# GyroAccel.net
KiCad netlist of a schematic drawn in Altium Designer
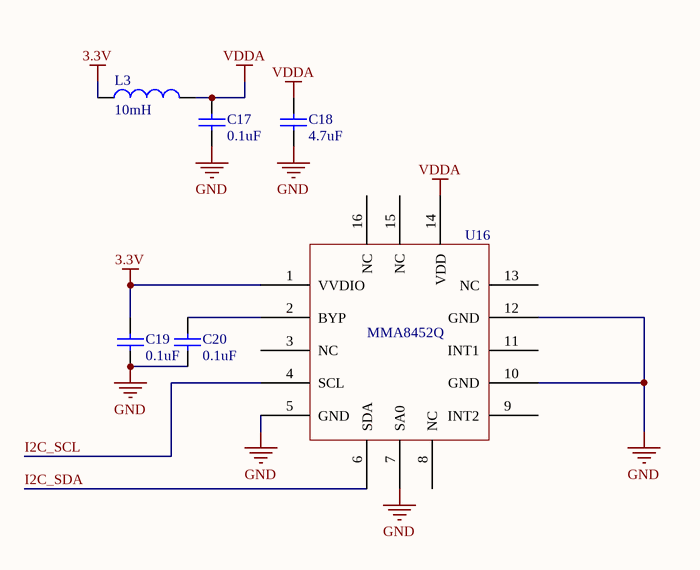
[diagram p0: GyroAccel.SchDoc]

(export (version "E")
  (design (tool "Eeschema 10.0.6"))
  (components
    (comp (ref "C17")
      (value "0.1uF")
      (footprint "CAPC1005L")
      (description "Capacitor (Semiconductor SIM Model)")
      (fields (field (name "Comment") "Cap Semi") (field (name "PUBLISHER") "Altium Limited"))
      (libsource (lib "Miscellaneous Devices") (part "Cap Semi"))
    )
    (comp (ref "C18")
      (value "4.7uF")
      (footprint "CAPC1608L")
      (description "Capacitor (Semiconductor SIM Model)")
      (fields (field (name "Comment") "Cap Semi") (field (name "PUBLISHER") "Altium Limited"))
      (libsource (lib "Miscellaneous Devices") (part "Cap Semi"))
    )
    (comp (ref "C19")
      (value "0.1uF")
      (footprint "CAPC1005L")
      (description "Capacitor (Semiconductor SIM Model)")
      (fields (field (name "Comment") "Cap Semi") (field (name "PUBLISHER") "Altium Limited"))
      (libsource (lib "Miscellaneous Devices") (part "Cap Semi"))
    )
    (comp (ref "C20")
      (value "0.1uF")
      (footprint "CAPC1005L")
      (description "Capacitor (Semiconductor SIM Model)")
      (fields (field (name "Comment") "Cap Semi") (field (name "PUBLISHER") "Altium Limited"))
      (libsource (lib "Miscellaneous Devices") (part "Cap Semi"))
    )
    (comp (ref "L3")
      (value "10mH")
      (footprint "INDC2012L")
      (description "Inductor")
      (fields (field (name "PUBLISHER") "Altium Limited"))
      (libsource (lib "Miscellaneous Devices") (part "Inductor"))
    )
    (comp (ref "U16") (value "MMA8452Q") (footprint "MMA8452Q") (libsource (lib "mrone") (part "MMA8452Q")))
  )
  (nets
    (net (code "1") (name "/I2C_SCL") (class "Default")
      (node (ref "U16") (pin "4") (pinfunction "SCL_4") (pintype "passive"))
    )
    (net (code "2") (name "/I2C_SDA") (class "Default")
      (node (ref "U16") (pin "6") (pinfunction "SDA_6") (pintype "passive"))
    )
    (net (code "3") (name "3.3V") (class "Default")
      (node (ref "C19") (pin "2") (pinfunction "2_2") (pintype "passive"))
      (node (ref "L3") (pin "2") (pinfunction "2_2") (pintype "passive"))
      (node (ref "U16") (pin "1") (pinfunction "VVDIO_1") (pintype "passive"))
    )
    (net (code "4") (name "GND") (class "Default")
      (node (ref "C17") (pin "1") (pinfunction "1_1") (pintype "passive"))
      (node (ref "C18") (pin "1") (pinfunction "1_1") (pintype "passive"))
      (node (ref "C19") (pin "1") (pinfunction "1_1") (pintype "passive"))
      (node (ref "C20") (pin "1") (pinfunction "1_1") (pintype "passive"))
      (node (ref "U16") (pin "10") (pinfunction "GND_10") (pintype "passive"))
      (node (ref "U16") (pin "12") (pinfunction "GND_12") (pintype "passive"))
      (node (ref "U16") (pin "5") (pinfunction "GND_5") (pintype "passive"))
      (node (ref "U16") (pin "7") (pinfunction "SA0_7") (pintype "passive"))
    )
    (net (code "5") (name "Net-(U16-BYP)") (class "Default")
      (node (ref "C20") (pin "2") (pinfunction "2_2") (pintype "passive"))
      (node (ref "U16") (pin "2") (pinfunction "BYP_2") (pintype "passive"))
    )
    (net (code "6") (name "VDDA") (class "Default")
      (node (ref "C17") (pin "2") (pinfunction "2_2") (pintype "passive"))
      (node (ref "C18") (pin "2") (pinfunction "2_2") (pintype "passive"))
      (node (ref "L3") (pin "1") (pinfunction "1_1") (pintype "passive"))
      (node (ref "U16") (pin "14") (pinfunction "VDD_14") (pintype "passive"))
    )
    (net (code "7") (name "unconnected-(U16-INT1-Pad11)") (class "Default")
      (node (ref "U16") (pin "11") (pinfunction "INT1_11") (pintype "passive"))
    )
    (net (code "8") (name "unconnected-(U16-INT2-Pad9)") (class "Default")
      (node (ref "U16") (pin "9") (pinfunction "INT2_9") (pintype "passive"))
    )
    (net (code "9") (name "unconnected-(U16-NC-Pad3)") (class "Default")
      (node (ref "U16") (pin "3") (pinfunction "NC_3") (pintype "passive"))
    )
    (net (code "10") (name "unconnected-(U16-NC-Pad8)") (class "Default")
      (node (ref "U16") (pin "8") (pinfunction "NC_8") (pintype "passive"))
    )
    (net (code "11") (name "unconnected-(U16-NC-Pad13)") (class "Default")
      (node (ref "U16") (pin "13") (pinfunction "NC_13") (pintype "passive"))
    )
    (net (code "12") (name "unconnected-(U16-NC-Pad15)") (class "Default")
      (node (ref "U16") (pin "15") (pinfunction "NC_15") (pintype "passive"))
    )
    (net (code "13") (name "unconnected-(U16-NC-Pad16)") (class "Default")
      (node (ref "U16") (pin "16") (pinfunction "NC_16") (pintype "passive"))
    )
  )
)
